# 8_ports.net
KiCad netlist of a schematic drawn in Altium Designer
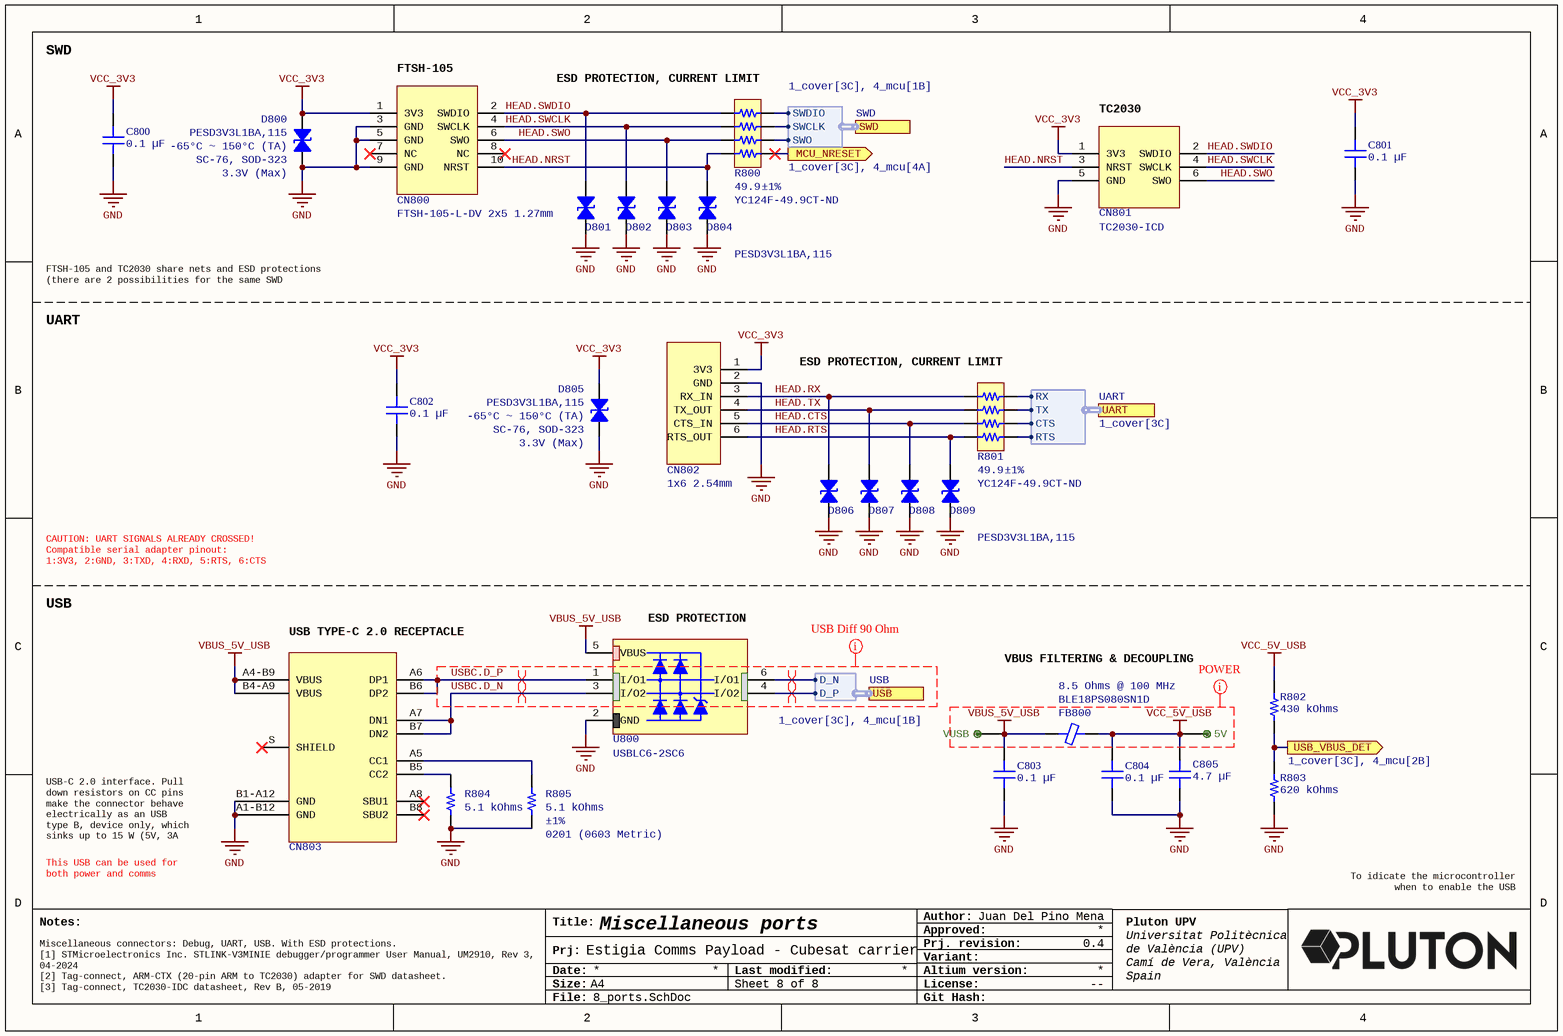
[diagram p0: 8_ports.SchDoc]

(export (version "E")
  (design (tool "Eeschema 10.0.6"))
  (components
    (comp (ref "5V")
      (value "~")
      (footprint "testpoints:testpoint_via")
      (description "Test point, thru-hole")
      (libsource (lib "testpoints") (part "TestPoint-VIA"))
    )
    (comp (ref "C800")
      (value "0.1 µF")
      (footprint "CAP 0402_1005")
      (description "CAP CER 0402 0.1UF 16V X7R 10%")
      (fields (field (name "PART NUMBER") "C0402C104K4RECAUTO") (field (name "MANUFACTURER") "KEMET"))
      (libsource (lib "Celestial Altium Library - altium_library") (part "Capacitor"))
    )
    (comp (ref "C801")
      (value "0.1 µF")
      (footprint "CAP 0402_1005")
      (description "CAP CER 0402 0.1UF 16V X7R 10%")
      (fields (field (name "PART NUMBER") "C0402C104K4RECAUTO") (field (name "MANUFACTURER") "KEMET"))
      (libsource (lib "Celestial Altium Library - altium_library") (part "Capacitor"))
    )
    (comp (ref "C802")
      (value "0.1 µF")
      (footprint "CAP 0402_1005")
      (description "CAP CER 0402 0.1UF 16V X7R 10%")
      (fields (field (name "PART NUMBER") "C0402C104K4RECAUTO") (field (name "MANUFACTURER") "KEMET"))
      (libsource (lib "Celestial Altium Library - altium_library") (part "Capacitor"))
    )
    (comp (ref "C803")
      (value "0.1 µF")
      (footprint "CAP 0402_1005")
      (description "CAP CER 0402 0.1UF 16V X7R 10%")
      (fields (field (name "PART NUMBER") "C0402C104K4RECAUTO") (field (name "MANUFACTURER") "KEMET"))
      (libsource (lib "Celestial Altium Library - altium_library") (part "Capacitor"))
    )
    (comp (ref "C804")
      (value "0.1 µF")
      (footprint "CAP 0402_1005")
      (description "CAP CER 0402 0.1UF 16V X7R 10%")
      (fields (field (name "PART NUMBER") "C0402C104K4RECAUTO") (field (name "MANUFACTURER") "KEMET"))
      (libsource (lib "Celestial Altium Library - altium_library") (part "Capacitor"))
    )
    (comp (ref "C805")
      (value "4.7 µF")
      (footprint "CAP 0603_1608")
      (description "CAP CER 4.7UF 16V X7R 0603")
      (fields
        (field (name "PART NUMBER") "GRM188Z71C475KE21J")
        (field (name "MANUFACTURER") "Murata Electronics")
      )
      (libsource (lib "Celestial Altium Library - altium_library") (part "Capacitor"))
    )
    (comp (ref "CN800")
      (value "FTSH-105-L-DV 2x5 1.27mm")
      (footprint "connectors:Samtec ftsh-105-l-dv")
      (description "Samtec FTSH-105-L-DV")
      (libsource (lib "connectors") (part "SWD Header 2x5 1.27mm"))
    )
    (comp (ref "CN801")
      (value "TC2030-ICD")
      (footprint "TC2030-MCP-NL")
      (libsource (lib "TC2030") (part "TC2030-ICD"))
    )
    (comp (ref "CN802")
      (value "1x6 2.54mm")
      (footprint "CONNECTORS:Header 1x6 2.54mm")
      (description "Header 1x6 2.54mm")
      (libsource (lib "connectors") (part "UART Header 1x6 2.54mm"))
    )
    (comp (ref "CN803")
      (value "USB4105-GF-A")
      (footprint "connectors:USB4105-GF-A")
      (libsource (lib "usb") (part "USB-C USB4105-GF-A"))
    )
    (comp (ref "D800")
      (value "PESD3V3L1BA,115")
      (footprint "SOD323")
      (description "TVS DIODE 3.3VWM 26VC SOD323")
      (fields
        (field (name "PART NUMBER") "PESD3V3L1BA,115")
        (field (name "MANUFACTURER") "Nexperia USA Inc.")
        (field (name "OPERATING TEMPERATURE") "-65°C ~ 150°C (TA)")
        (field (name "PACKAGE / CASE") "SC-76, SOD-323")
        (field (name "VOLTAGE - REVERSE STANDOFF (TYP)") "3.3V (Max)")
      )
      (libsource (lib "Celestial Altium Library - altium_library") (part "Diode TVS"))
    )
    (comp (ref "D801")
      (value "PESD3V3L1BA,115")
      (footprint "SOD323")
      (description "TVS DIODE 3.3VWM 26VC SOD323")
      (fields (field (name "MANUFACTURER") "Nexperia USA Inc."))
      (libsource (lib "Celestial Altium Library - altium_library") (part "Diode TVS"))
    )
    (comp (ref "D802")
      (value "PESD3V3L1BA,115")
      (footprint "SOD323")
      (description "TVS DIODE 3.3VWM 26VC SOD323")
      (fields (field (name "MANUFACTURER") "Nexperia USA Inc."))
      (libsource (lib "Celestial Altium Library - altium_library") (part "Diode TVS"))
    )
    (comp (ref "D803")
      (value "PESD3V3L1BA,115")
      (footprint "SOD323")
      (description "TVS DIODE 3.3VWM 26VC SOD323")
      (fields (field (name "MANUFACTURER") "Nexperia USA Inc."))
      (libsource (lib "Celestial Altium Library - altium_library") (part "Diode TVS"))
    )
    (comp (ref "D804")
      (value "PESD3V3L1BA,115")
      (footprint "SOD323")
      (description "TVS DIODE 3.3VWM 26VC SOD323")
      (fields
        (field (name "PART NUMBER") "PESD3V3L1BA,115")
        (field (name "MANUFACTURER") "Nexperia USA Inc.")
      )
      (libsource (lib "Celestial Altium Library - altium_library") (part "Diode TVS"))
    )
    (comp (ref "D805")
      (value "PESD3V3L1BA,115")
      (footprint "SOD323")
      (description "TVS DIODE 3.3VWM 26VC SOD323")
      (fields
        (field (name "PART NUMBER") "PESD3V3L1BA,115")
        (field (name "MANUFACTURER") "Nexperia USA Inc.")
        (field (name "OPERATING TEMPERATURE") "-65°C ~ 150°C (TA)")
        (field (name "PACKAGE / CASE") "SC-76, SOD-323")
        (field (name "VOLTAGE - REVERSE STANDOFF (TYP)") "3.3V (Max)")
      )
      (libsource (lib "Celestial Altium Library - altium_library") (part "Diode TVS"))
    )
    (comp (ref "D806")
      (value "PESD3V3L1BA,115")
      (footprint "SOD323")
      (description "TVS DIODE 3.3VWM 26VC SOD323")
      (fields (field (name "MANUFACTURER") "Nexperia USA Inc."))
      (libsource (lib "Celestial Altium Library - altium_library") (part "Diode TVS"))
    )
    (comp (ref "D807")
      (value "PESD3V3L1BA,115")
      (footprint "SOD323")
      (description "TVS DIODE 3.3VWM 26VC SOD323")
      (fields (field (name "MANUFACTURER") "Nexperia USA Inc."))
      (libsource (lib "Celestial Altium Library - altium_library") (part "Diode TVS"))
    )
    (comp (ref "D808")
      (value "PESD3V3L1BA,115")
      (footprint "SOD323")
      (description "TVS DIODE 3.3VWM 26VC SOD323")
      (fields (field (name "MANUFACTURER") "Nexperia USA Inc."))
      (libsource (lib "Celestial Altium Library - altium_library") (part "Diode TVS"))
    )
    (comp (ref "D809")
      (value "PESD3V3L1BA,115")
      (footprint "SOD323")
      (description "TVS DIODE 3.3VWM 26VC SOD323")
      (fields
        (field (name "PART NUMBER") "PESD3V3L1BA,115")
        (field (name "MANUFACTURER") "Nexperia USA Inc.")
      )
      (libsource (lib "Celestial Altium Library - altium_library") (part "Diode TVS"))
    )
    (comp (ref "FB800")
      (value "8.5 Ohms @ 100 MHz")
      (footprint "FER 0603_1608")
      (description "FERRITE BEAD 8.5 OHM 0603 1LN")
      (fields
        (field (name "PART NUMBER") "BLE18PS080SN1D")
        (field (name "IMPEDANCE @ FREQUENCY") "8.5 Ohms @ 100 MHz")
        (field (name "MANUFACTURER") "Murata Electronics")
      )
      (libsource (lib "Celestial Altium Library - altium_library") (part "Ferrite Chip"))
    )
    (comp (ref "R800")
      (value "YC124-FR-0749R9L")
      (footprint "RESNET 0804-8 CONVEX")
      (description "RES ARRAY 4 RES 49.9 OHM 0804")
      (fields
        (field (name "MANUFACTURER") "Yageo")
        (field (name "RESISTANCE (OHMS)") "49.9")
        (field (name "SUPPLIER PART NUMBER 1") "YC124F-49.9CT-ND")
        (field (name "TOLERANCE") "±1%")
      )
      (libsource (lib "Celestial Altium Library - altium_library") (part "Resistor Array (4 circuit)"))
    )
    (comp (ref "R801")
      (value "YC124-FR-0749R9L")
      (footprint "RESNET 0804-8 CONVEX")
      (description "RES ARRAY 4 RES 49.9 OHM 0804")
      (fields
        (field (name "MANUFACTURER") "Yageo")
        (field (name "RESISTANCE (OHMS)") "49.9")
        (field (name "SUPPLIER PART NUMBER 1") "YC124F-49.9CT-ND")
        (field (name "TOLERANCE") "±1%")
      )
      (libsource (lib "Celestial Altium Library - altium_library") (part "Resistor Array (4 circuit)"))
    )
    (comp (ref "R802")
      (value "430 kOhms")
      (footprint "RES 0201_0603")
      (description "RES SMD 430K OHM 1% 1/20W 0201")
      (fields
        (field (name "PART NUMBER") "ERJ-1GNF4303C")
        (field (name "MANUFACTURER") "Panasonic Electronic Components")
      )
      (libsource (lib "Celestial Altium Library - altium_library") (part "Resistor"))
    )
    (comp (ref "R803")
      (value "620 kOhms")
      (footprint "RES 0201_0603")
      (description "RES SMD 620K OHM 1% 1/20W 0201")
      (fields
        (field (name "PART NUMBER") "ERJ-1GNF6203C")
        (field (name "MANUFACTURER") "Panasonic Electronic Components")
      )
      (libsource (lib "Celestial Altium Library - altium_library") (part "Resistor"))
    )
    (comp (ref "R804")
      (value "5.1 kOhms")
      (footprint "RES 0201_0603")
      (description "RES SMD 5.1K OHM 1% 1/20W 0201")
      (fields (field (name "PART NUMBER") "AC0201FR-075K1L") (field (name "MANUFACTURER") "Yageo"))
      (libsource (lib "Celestial Altium Library - altium_library") (part "Resistor"))
    )
    (comp (ref "R805")
      (value "5.1 kOhms")
      (footprint "RES 0201_0603")
      (description "RES SMD 5.1K OHM 1% 1/20W 0201")
      (fields
        (field (name "PART NUMBER") "AC0201FR-075K1L")
        (field (name "DEVICE PACKAGE") "0201 (0603 Metric)")
        (field (name "MANUFACTURER") "Yageo")
        (field (name "TOLERANCE") "±1%")
      )
      (libsource (lib "Celestial Altium Library - altium_library") (part "Resistor"))
    )
    (comp (ref "U800")
      (value "USBLC6-2SC6")
      (footprint "ics:SOT23-6L")
      (libsource (lib "usb") (part "USBLC6-2SC6"))
    )
    (comp (ref "VUSB")
      (value "~")
      (footprint "testpoints:testpoint_via")
      (description "Test point, thru-hole")
      (libsource (lib "testpoints") (part "TestPoint-VIA"))
    )
  )
  (nets
    (net (code "4") (name "/CTS") (class "Default")
      (node (ref "R801") (pin "6") (pinfunction "6_6") (pintype "passive"))
    )
    (net (code "5") (name "/D_N") (class "Default")
      (node (ref "U800") (pin "6") (pinfunction "I/O1_6") (pintype "passive"))
    )
    (net (code "6") (name "/D_P") (class "Default")
      (node (ref "U800") (pin "4") (pinfunction "I/O2_4") (pintype "passive"))
    )
    (net (code "7") (name "/HEAD.CTS") (class "Default")
      (node (ref "CN802") (pin "5") (pinfunction "CTS_IN_5") (pintype "passive"))
      (node (ref "D808") (pin "2") (pinfunction "2_2") (pintype "passive"))
      (node (ref "R801") (pin "3") (pinfunction "3_3") (pintype "passive"))
    )
    (net (code "8") (name "/HEAD.NRST") (class "Default")
      (node (ref "CN800") (pin "10") (pinfunction "NRST_10") (pintype "passive"))
      (node (ref "CN801") (pin "3") (pinfunction "NRST_3") (pintype "passive"))
      (node (ref "D804") (pin "2") (pinfunction "2_2") (pintype "passive"))
      (node (ref "R800") (pin "4") (pinfunction "4_4") (pintype "passive"))
    )
    (net (code "9") (name "/HEAD.RTS") (class "Default")
      (node (ref "CN802") (pin "6") (pinfunction "RTS_OUT_6") (pintype "passive"))
      (node (ref "D809") (pin "2") (pinfunction "2_2") (pintype "passive"))
      (node (ref "R801") (pin "4") (pinfunction "4_4") (pintype "passive"))
    )
    (net (code "10") (name "/HEAD.RX") (class "Default")
      (node (ref "CN802") (pin "3") (pinfunction "RX_IN_3") (pintype "passive"))
      (node (ref "D806") (pin "2") (pinfunction "2_2") (pintype "passive"))
      (node (ref "R801") (pin "1") (pinfunction "1_1") (pintype "passive"))
    )
    (net (code "11") (name "/HEAD.SWCLK") (class "Default")
      (node (ref "CN800") (pin "4") (pinfunction "SWCLK_4") (pintype "passive"))
      (node (ref "CN801") (pin "4") (pinfunction "SWCLK_4") (pintype "passive"))
      (node (ref "D802") (pin "2") (pinfunction "2_2") (pintype "passive"))
      (node (ref "R800") (pin "2") (pinfunction "2_2") (pintype "passive"))
    )
    (net (code "12") (name "/HEAD.SWDIO") (class "Default")
      (node (ref "CN800") (pin "2") (pinfunction "SWDIO_2") (pintype "passive"))
      (node (ref "CN801") (pin "2") (pinfunction "SWDIO_2") (pintype "passive"))
      (node (ref "D801") (pin "2") (pinfunction "2_2") (pintype "passive"))
      (node (ref "R800") (pin "1") (pinfunction "1_1") (pintype "passive"))
    )
    (net (code "13") (name "/HEAD.SWO") (class "Default")
      (node (ref "CN800") (pin "6") (pinfunction "SWO_6") (pintype "passive"))
      (node (ref "CN801") (pin "6") (pinfunction "SWO_6") (pintype "passive"))
      (node (ref "D803") (pin "2") (pinfunction "2_2") (pintype "passive"))
      (node (ref "R800") (pin "3") (pinfunction "3_3") (pintype "passive"))
    )
    (net (code "14") (name "/HEAD.TX") (class "Default")
      (node (ref "CN802") (pin "4") (pinfunction "TX_OUT_4") (pintype "passive"))
      (node (ref "D807") (pin "2") (pinfunction "2_2") (pintype "passive"))
      (node (ref "R801") (pin "2") (pinfunction "2_2") (pintype "passive"))
    )
    (net (code "15") (name "/MCU_NRESET") (class "Default")
      (node (ref "R800") (pin "5") (pinfunction "5_5") (pintype "passive+no_connect"))
    )
    (net (code "16") (name "/RTS") (class "Default")
      (node (ref "R801") (pin "5") (pinfunction "5_5") (pintype "passive"))
    )
    (net (code "17") (name "/RX") (class "Default")
      (node (ref "R801") (pin "8") (pinfunction "8_8") (pintype "passive"))
    )
    (net (code "18") (name "/SWCLK") (class "Default")
      (node (ref "R800") (pin "7") (pinfunction "7_7") (pintype "passive"))
    )
    (net (code "19") (name "/SWDIO") (class "Default")
      (node (ref "R800") (pin "8") (pinfunction "8_8") (pintype "passive"))
    )
    (net (code "20") (name "/SWO") (class "Default")
      (node (ref "R800") (pin "6") (pinfunction "6_6") (pintype "passive"))
    )
    (net (code "21") (name "/TX") (class "Default")
      (node (ref "R801") (pin "7") (pinfunction "7_7") (pintype "passive"))
    )
    (net (code "22") (name "/USBC.D_N") (class "Default")
      (node (ref "CN803") (pin "A7") (pinfunction "DN1_A7") (pintype "passive"))
      (node (ref "CN803") (pin "B7") (pinfunction "DN2_B7") (pintype "passive"))
      (node (ref "U800") (pin "3") (pinfunction "I/O2_3") (pintype "passive"))
    )
    (net (code "23") (name "/USBC.D_P") (class "Default")
      (node (ref "CN803") (pin "A6") (pinfunction "DP1_A6") (pintype "passive"))
      (node (ref "CN803") (pin "B6") (pinfunction "DP2_B6") (pintype "passive"))
      (node (ref "U800") (pin "1") (pinfunction "I/O1_1") (pintype "passive"))
    )
    (net (code "24") (name "/USB_VBUS_DET") (class "Default")
      (node (ref "R802") (pin "1") (pinfunction "1_1") (pintype "passive"))
      (node (ref "R803") (pin "2") (pinfunction "2_2") (pintype "passive"))
    )
    (net (code "28") (name "GND") (class "Default")
      (node (ref "C800") (pin "1") (pinfunction "1_1") (pintype "passive"))
      (node (ref "C801") (pin "1") (pinfunction "1_1") (pintype "passive"))
      (node (ref "C802") (pin "1") (pinfunction "1_1") (pintype "passive"))
      (node (ref "C803") (pin "1") (pinfunction "1_1") (pintype "passive"))
      (node (ref "C804") (pin "1") (pinfunction "1_1") (pintype "passive"))
      (node (ref "C805") (pin "1") (pinfunction "1_1") (pintype "passive"))
      (node (ref "CN800") (pin "3") (pinfunction "GND_3") (pintype "passive"))
      (node (ref "CN800") (pin "5") (pinfunction "GND_5") (pintype "passive"))
      (node (ref "CN800") (pin "9") (pinfunction "GND_9") (pintype "passive"))
      (node (ref "CN801") (pin "5") (pinfunction "GND_5") (pintype "passive"))
      (node (ref "CN802") (pin "2") (pinfunction "GND_2") (pintype "power_in"))
      (node (ref "CN803") (pin "A1-B12") (pinfunction "GND_A1-B12") (pintype "power_in"))
      (node (ref "CN803") (pin "B1-A12") (pinfunction "GND_B1-A12") (pintype "power_in"))
      (node (ref "D800") (pin "1") (pinfunction "1_1") (pintype "passive"))
      (node (ref "D801") (pin "1") (pinfunction "1_1") (pintype "passive"))
      (node (ref "D802") (pin "1") (pinfunction "1_1") (pintype "passive"))
      (node (ref "D803") (pin "1") (pinfunction "1_1") (pintype "passive"))
      (node (ref "D804") (pin "1") (pinfunction "1_1") (pintype "passive"))
      (node (ref "D805") (pin "1") (pinfunction "1_1") (pintype "passive"))
      (node (ref "D806") (pin "1") (pinfunction "1_1") (pintype "passive"))
      (node (ref "D807") (pin "1") (pinfunction "1_1") (pintype "passive"))
      (node (ref "D808") (pin "1") (pinfunction "1_1") (pintype "passive"))
      (node (ref "D809") (pin "1") (pinfunction "1_1") (pintype "passive"))
      (node (ref "R803") (pin "1") (pinfunction "1_1") (pintype "passive"))
      (node (ref "R804") (pin "1") (pinfunction "1_1") (pintype "passive"))
      (node (ref "R805") (pin "1") (pinfunction "1_1") (pintype "passive"))
      (node (ref "U800") (pin "2") (pinfunction "GND_2") (pintype "passive"))
    )
    (net (code "29") (name "Net-(CN803-CC1)") (class "Default")
      (node (ref "CN803") (pin "A5") (pinfunction "CC1_A5") (pintype "passive"))
      (node (ref "R805") (pin "2") (pinfunction "2_2") (pintype "passive"))
    )
    (net (code "30") (name "Net-(CN803-CC2)") (class "Default")
      (node (ref "CN803") (pin "B5") (pinfunction "CC2_B5") (pintype "passive"))
      (node (ref "R804") (pin "2") (pinfunction "2_2") (pintype "passive"))
    )
    (net (code "31") (name "VBUS_5V_USB") (class "Default")
      (node (ref "C803") (pin "2") (pinfunction "2_2") (pintype "passive"))
      (node (ref "CN803") (pin "A4-B9") (pinfunction "VBUS_A4-B9") (pintype "power_in"))
      (node (ref "CN803") (pin "B4-A9") (pinfunction "VBUS_B4-A9") (pintype "power_in"))
      (node (ref "FB800") (pin "1") (pinfunction "1_1") (pintype "passive"))
      (node (ref "U800") (pin "5") (pinfunction "VBUS_5") (pintype "passive"))
      (node (ref "VUSB") (pin "0") (pinfunction "0_0") (pintype "passive"))
    )
    (net (code "32") (name "VCC_3V3") (class "Default")
      (node (ref "C800") (pin "2") (pinfunction "2_2") (pintype "passive"))
      (node (ref "C801") (pin "2") (pinfunction "2_2") (pintype "passive"))
      (node (ref "C802") (pin "2") (pinfunction "2_2") (pintype "passive"))
      (node (ref "CN800") (pin "1") (pinfunction "3V3_1") (pintype "passive"))
      (node (ref "CN801") (pin "1") (pinfunction "3V3_1") (pintype "passive"))
      (node (ref "CN802") (pin "1") (pinfunction "3V3_1") (pintype "power_in"))
      (node (ref "D800") (pin "2") (pinfunction "2_2") (pintype "passive"))
      (node (ref "D805") (pin "2") (pinfunction "2_2") (pintype "passive"))
    )
    (net (code "33") (name "VCC_5V_USB") (class "Default")
      (node (ref "5V") (pin "0") (pinfunction "0_0") (pintype "passive"))
      (node (ref "C804") (pin "2") (pinfunction "2_2") (pintype "passive"))
      (node (ref "C805") (pin "2") (pinfunction "2_2") (pintype "passive"))
      (node (ref "FB800") (pin "2") (pinfunction "2_2") (pintype "passive"))
      (node (ref "R802") (pin "2") (pinfunction "2_2") (pintype "passive"))
    )
    (net (code "34") (name "unconnected-(CN800-NC-Pad7)") (class "Default")
      (node (ref "CN800") (pin "7") (pinfunction "NC_7") (pintype "passive+no_connect"))
    )
    (net (code "35") (name "unconnected-(CN800-NC-Pad8)") (class "Default")
      (node (ref "CN800") (pin "8") (pinfunction "NC_8") (pintype "passive+no_connect"))
    )
    (net (code "36") (name "unconnected-(CN803-SBU1-PadA8)") (class "Default")
      (node (ref "CN803") (pin "A8") (pinfunction "SBU1_A8") (pintype "passive+no_connect"))
    )
    (net (code "37") (name "unconnected-(CN803-SBU2-PadB8)") (class "Default")
      (node (ref "CN803") (pin "B8") (pinfunction "SBU2_B8") (pintype "passive+no_connect"))
    )
    (net (code "38") (name "unconnected-(CN803-SHIELD-PadS)") (class "Default")
      (node (ref "CN803") (pin "S") (pinfunction "SHIELD_S") (pintype "passive+no_connect"))
    )
  )
)
